# 01-MCU-V2_4.net
KiCad netlist of a schematic drawn in Altium Designer
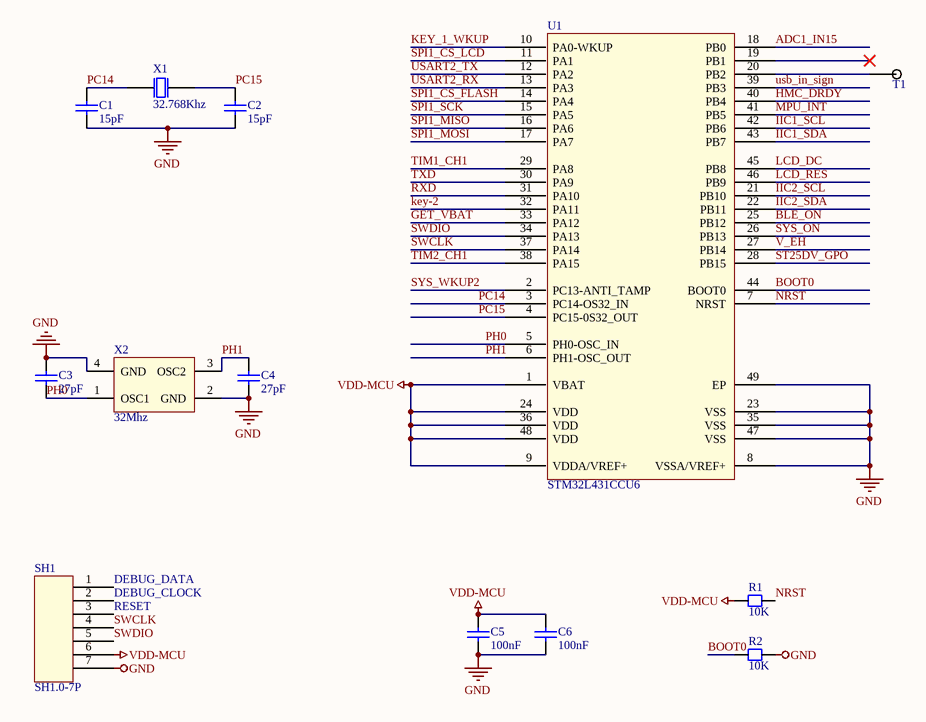
[diagram p0: 01-MCU-V2.4.SchDoc]

(export (version "E")
  (design (tool "Eeschema 10.0.6"))
  (components
    (comp (ref "C1")
      (value "15pF")
      (footprint "CC1005-0402")
      (description "贴片电容")
      (libsource (lib "tianxiaohua_Schlib") (part "Chip capacitor"))
    )
    (comp (ref "C2")
      (value "15pF")
      (footprint "CC1005-0402")
      (description "贴片电容")
      (libsource (lib "tianxiaohua_Schlib") (part "Chip capacitor"))
    )
    (comp (ref "C3")
      (value "27pF")
      (footprint "CC1005-0402")
      (description "贴片电容")
      (libsource (lib "tianxiaohua_Schlib") (part "Chip capacitor"))
    )
    (comp (ref "C4")
      (value "27pF")
      (footprint "CC1005-0402")
      (description "贴片电容")
      (libsource (lib "tianxiaohua_Schlib") (part "Chip capacitor"))
    )
    (comp (ref "C5")
      (value "100nF")
      (footprint "CC1005-0402")
      (description "贴片电容")
      (libsource (lib "tianxiaohua_Schlib") (part "Chip capacitor"))
    )
    (comp (ref "C6")
      (value "100nF")
      (footprint "CC1005-0402")
      (description "贴片电容")
      (libsource (lib "tianxiaohua_Schlib") (part "Chip capacitor"))
    )
    (comp (ref "R1")
      (value "10K")
      (footprint "CR1005-0402")
      (description "贴片电阻")
      (libsource (lib "tianxiaohua_Schlib") (part "Chip resistor"))
    )
    (comp (ref "R2")
      (value "10K")
      (footprint "CR1005-0402")
      (description "贴片电阻")
      (libsource (lib "tianxiaohua_Schlib") (part "Chip resistor"))
    )
    (comp (ref "SH1")
      (value "SH1.0-7P")
      (footprint "SH1.0-7P")
      (description "间距为1mm的端子")
      (libsource (lib "tianxiaohua_Schlib") (part "SH1.0-7P"))
    )
    (comp (ref "T1") (value "测试点") (footprint "测试点") (libsource (lib "tianxiaohua_Schlib") (part "测试点")))
    (comp (ref "U1")
      (value "STM32L431CCU6")
      (footprint "STM32-UFQFPN48_N")
      (description "stm32低功耗单片机 主频80MHz")
      (libsource (lib "tianxiaohua_Schlib") (part "STM32L431CCU6"))
    )
    (comp (ref "X1")
      (value "32.768Khz")
      (footprint "XTAL-2012")
      (description "2012封装的时钟晶振")
      (libsource (lib "tianxiaohua_Schlib") (part "XTAL 2012"))
    )
    (comp (ref "X2")
      (value "32Mhz")
      (footprint "XTAL-2016")
      (description "2016封装的晶振")
      (libsource (lib "tianxiaohua_Schlib") (part "XTAL 2016"))
    )
  )
  (nets
    (net (code "1") (name "/ADC1_IN15") (class "Default")
      (node (ref "U1") (pin "18") (pinfunction "PB0_18") (pintype "passive"))
    )
    (net (code "2") (name "/BLE_ON") (class "Default")
      (node (ref "U1") (pin "25") (pinfunction "PB12_25") (pintype "passive"))
    )
    (net (code "3") (name "/BOOT0") (class "Default")
      (node (ref "R2") (pin "2") (pinfunction "2_2") (pintype "passive"))
      (node (ref "U1") (pin "44") (pinfunction "BOOT0_44") (pintype "passive"))
    )
    (net (code "4") (name "/DEBUG_CLOCK") (class "Default")
      (node (ref "SH1") (pin "2") (pinfunction "2_2") (pintype "passive"))
    )
    (net (code "5") (name "/DEBUG_DATA") (class "Default") (node (ref "SH1") (pin "1") (pintype "passive")))
    (net (code "6") (name "/GET_VBAT") (class "Default")
      (node (ref "U1") (pin "33") (pinfunction "PA12_33") (pintype "passive"))
    )
    (net (code "7") (name "/HMC_DRDY") (class "Default")
      (node (ref "U1") (pin "40") (pinfunction "PB4_40") (pintype "passive"))
    )
    (net (code "8") (name "/IIC1_SCL") (class "Default")
      (node (ref "U1") (pin "42") (pinfunction "PB6_42") (pintype "passive"))
    )
    (net (code "9") (name "/IIC1_SDA") (class "Default")
      (node (ref "U1") (pin "43") (pinfunction "PB7_43") (pintype "passive"))
    )
    (net (code "10") (name "/IIC2_SCL") (class "Default")
      (node (ref "U1") (pin "21") (pinfunction "PB10_21") (pintype "passive"))
    )
    (net (code "11") (name "/IIC2_SDA") (class "Default")
      (node (ref "U1") (pin "22") (pinfunction "PB11_22") (pintype "passive"))
    )
    (net (code "12") (name "/KEY_1_WKUP") (class "Default")
      (node (ref "U1") (pin "10") (pinfunction "PA0-WKUP_10") (pintype "passive"))
    )
    (net (code "13") (name "/LCD_DC") (class "Default")
      (node (ref "U1") (pin "45") (pinfunction "PB8_45") (pintype "passive"))
    )
    (net (code "14") (name "/LCD_RES") (class "Default")
      (node (ref "U1") (pin "46") (pinfunction "PB9_46") (pintype "passive"))
    )
    (net (code "15") (name "/MPU_INT") (class "Default")
      (node (ref "U1") (pin "41") (pinfunction "PB5_41") (pintype "passive"))
    )
    (net (code "16") (name "/NRST") (class "Default")
      (node (ref "R1") (pin "1") (pinfunction "1_1") (pintype "passive"))
      (node (ref "U1") (pin "7") (pinfunction "NRST_7") (pintype "passive"))
    )
    (net (code "17") (name "/PC14") (class "Default")
      (node (ref "C1") (pin "2") (pinfunction "2_2") (pintype "passive"))
      (node (ref "U1") (pin "3") (pinfunction "PC14-OS32_IN_3") (pintype "passive"))
      (node (ref "X1") (pin "2") (pinfunction "2_2") (pintype "passive"))
    )
    (net (code "18") (name "/PC15") (class "Default")
      (node (ref "C2") (pin "2") (pinfunction "2_2") (pintype "passive"))
      (node (ref "U1") (pin "4") (pinfunction "PC15-0S32_OUT_4") (pintype "passive"))
      (node (ref "X1") (pin "1") (pinfunction "1_1") (pintype "passive"))
    )
    (net (code "19") (name "/PH0") (class "Default")
      (node (ref "C3") (pin "1") (pinfunction "1_1") (pintype "passive"))
      (node (ref "U1") (pin "5") (pinfunction "PH0-OSC_IN_5") (pintype "passive"))
      (node (ref "X2") (pin "1") (pinfunction "OSC1_1") (pintype "passive"))
    )
    (net (code "20") (name "/PH1") (class "Default")
      (node (ref "C4") (pin "2") (pinfunction "2_2") (pintype "passive"))
      (node (ref "U1") (pin "6") (pinfunction "PH1-OSC_OUT_6") (pintype "passive"))
      (node (ref "X2") (pin "3") (pinfunction "OSC2_3") (pintype "passive"))
    )
    (net (code "21") (name "/RESET") (class "Default") (node (ref "SH1") (pin "3") (pintype "passive")))
    (net (code "22") (name "/RXD") (class "Default")
      (node (ref "U1") (pin "31") (pinfunction "PA10_31") (pintype "passive"))
    )
    (net (code "23") (name "/SPI1_CS_FLASH") (class "Default")
      (node (ref "U1") (pin "14") (pinfunction "PA4_14") (pintype "passive"))
    )
    (net (code "24") (name "/SPI1_CS_LCD") (class "Default")
      (node (ref "U1") (pin "11") (pinfunction "PA1_11") (pintype "passive"))
    )
    (net (code "25") (name "/SPI1_MISO") (class "Default")
      (node (ref "U1") (pin "16") (pinfunction "PA6_16") (pintype "passive"))
    )
    (net (code "26") (name "/SPI1_MOSI") (class "Default")
      (node (ref "U1") (pin "17") (pinfunction "PA7_17") (pintype "passive"))
    )
    (net (code "27") (name "/SPI1_SCK") (class "Default")
      (node (ref "U1") (pin "15") (pinfunction "PA5_15") (pintype "passive"))
    )
    (net (code "28") (name "/ST25DV_GPO") (class "Default")
      (node (ref "U1") (pin "28") (pinfunction "PB15_28") (pintype "passive"))
    )
    (net (code "29") (name "/SWCLK") (class "Default")
      (node (ref "SH1") (pin "4") (pinfunction "4_4") (pintype "passive"))
      (node (ref "U1") (pin "37") (pinfunction "PA14_37") (pintype "passive"))
    )
    (net (code "30") (name "/SWDIO") (class "Default")
      (node (ref "SH1") (pin "5") (pintype "passive"))
      (node (ref "U1") (pin "34") (pinfunction "PA13_34") (pintype "passive"))
    )
    (net (code "31") (name "/SYS_ON") (class "Default")
      (node (ref "U1") (pin "26") (pinfunction "PB13_26") (pintype "passive"))
    )
    (net (code "32") (name "/SYS_WKUP2") (class "Default")
      (node (ref "U1") (pin "2") (pinfunction "PC13-ANTI_TAMP_2") (pintype "passive"))
    )
    (net (code "33") (name "/TIM1_CH1") (class "Default")
      (node (ref "U1") (pin "29") (pinfunction "PA8_29") (pintype "passive"))
    )
    (net (code "34") (name "/TIM2_CH1") (class "Default")
      (node (ref "U1") (pin "38") (pinfunction "PA15_38") (pintype "passive"))
    )
    (net (code "35") (name "/TXD") (class "Default")
      (node (ref "U1") (pin "30") (pinfunction "PA9_30") (pintype "passive"))
    )
    (net (code "36") (name "/USART2_RX") (class "Default")
      (node (ref "U1") (pin "13") (pinfunction "PA3_13") (pintype "passive"))
    )
    (net (code "37") (name "/USART2_TX") (class "Default")
      (node (ref "U1") (pin "12") (pinfunction "PA2_12") (pintype "passive"))
    )
    (net (code "38") (name "/V_EH") (class "Default")
      (node (ref "U1") (pin "27") (pinfunction "PB14_27") (pintype "passive"))
    )
    (net (code "39") (name "/key-2") (class "Default")
      (node (ref "U1") (pin "32") (pinfunction "PA11_32") (pintype "passive"))
    )
    (net (code "40") (name "/usb_in_sign") (class "Default")
      (node (ref "U1") (pin "39") (pinfunction "PB3_39") (pintype "passive"))
    )
    (net (code "41") (name "GND") (class "Default")
      (node (ref "C1") (pin "1") (pinfunction "1_1") (pintype "passive"))
      (node (ref "C2") (pin "1") (pinfunction "1_1") (pintype "passive"))
      (node (ref "C3") (pin "2") (pinfunction "2_2") (pintype "passive"))
      (node (ref "C4") (pin "1") (pinfunction "1_1") (pintype "passive"))
      (node (ref "C5") (pin "1") (pinfunction "1_1") (pintype "passive"))
      (node (ref "C6") (pin "1") (pinfunction "1_1") (pintype "passive"))
      (node (ref "R2") (pin "1") (pinfunction "1_1") (pintype "passive"))
      (node (ref "SH1") (pin "7") (pinfunction "7_7") (pintype "passive"))
      (node (ref "U1") (pin "23") (pinfunction "VSS_23") (pintype "passive"))
      (node (ref "U1") (pin "35") (pinfunction "VSS_35") (pintype "passive"))
      (node (ref "U1") (pin "47") (pinfunction "VSS_47") (pintype "passive"))
      (node (ref "U1") (pin "49") (pinfunction "EP_49") (pintype "passive"))
      (node (ref "U1") (pin "8") (pinfunction "VSSA/VREF+_8") (pintype "passive"))
      (node (ref "X2") (pin "2") (pinfunction "GND_2") (pintype "passive"))
      (node (ref "X2") (pin "4") (pinfunction "GND_4") (pintype "passive"))
    )
    (net (code "42") (name "Net-(U1-PB2)") (class "Default")
      (node (ref "T1") (pin "1") (pinfunction "1_1") (pintype "passive"))
      (node (ref "U1") (pin "20") (pinfunction "PB2_20") (pintype "passive"))
    )
    (net (code "43") (name "VDD-MCU") (class "Default")
      (node (ref "C5") (pin "2") (pinfunction "2_2") (pintype "passive"))
      (node (ref "C6") (pin "2") (pinfunction "2_2") (pintype "passive"))
      (node (ref "R1") (pin "2") (pinfunction "2_2") (pintype "passive"))
      (node (ref "SH1") (pin "6") (pinfunction "6_6") (pintype "passive"))
      (node (ref "U1") (pin "1") (pinfunction "VBAT_1") (pintype "passive"))
      (node (ref "U1") (pin "24") (pinfunction "VDD_24") (pintype "passive"))
      (node (ref "U1") (pin "36") (pinfunction "VDD_36") (pintype "passive"))
      (node (ref "U1") (pin "48") (pinfunction "VDD_48") (pintype "passive"))
      (node (ref "U1") (pin "9") (pinfunction "VDDA/VREF+_9") (pintype "passive"))
    )
    (net (code "44") (name "unconnected-(U1-PB1-Pad19)") (class "Default")
      (node (ref "U1") (pin "19") (pinfunction "PB1_19") (pintype "passive+no_connect"))
    )
  )
)
